# teensy-boom-jr.net
KiCad netlist of a schematic drawn in EAGLE
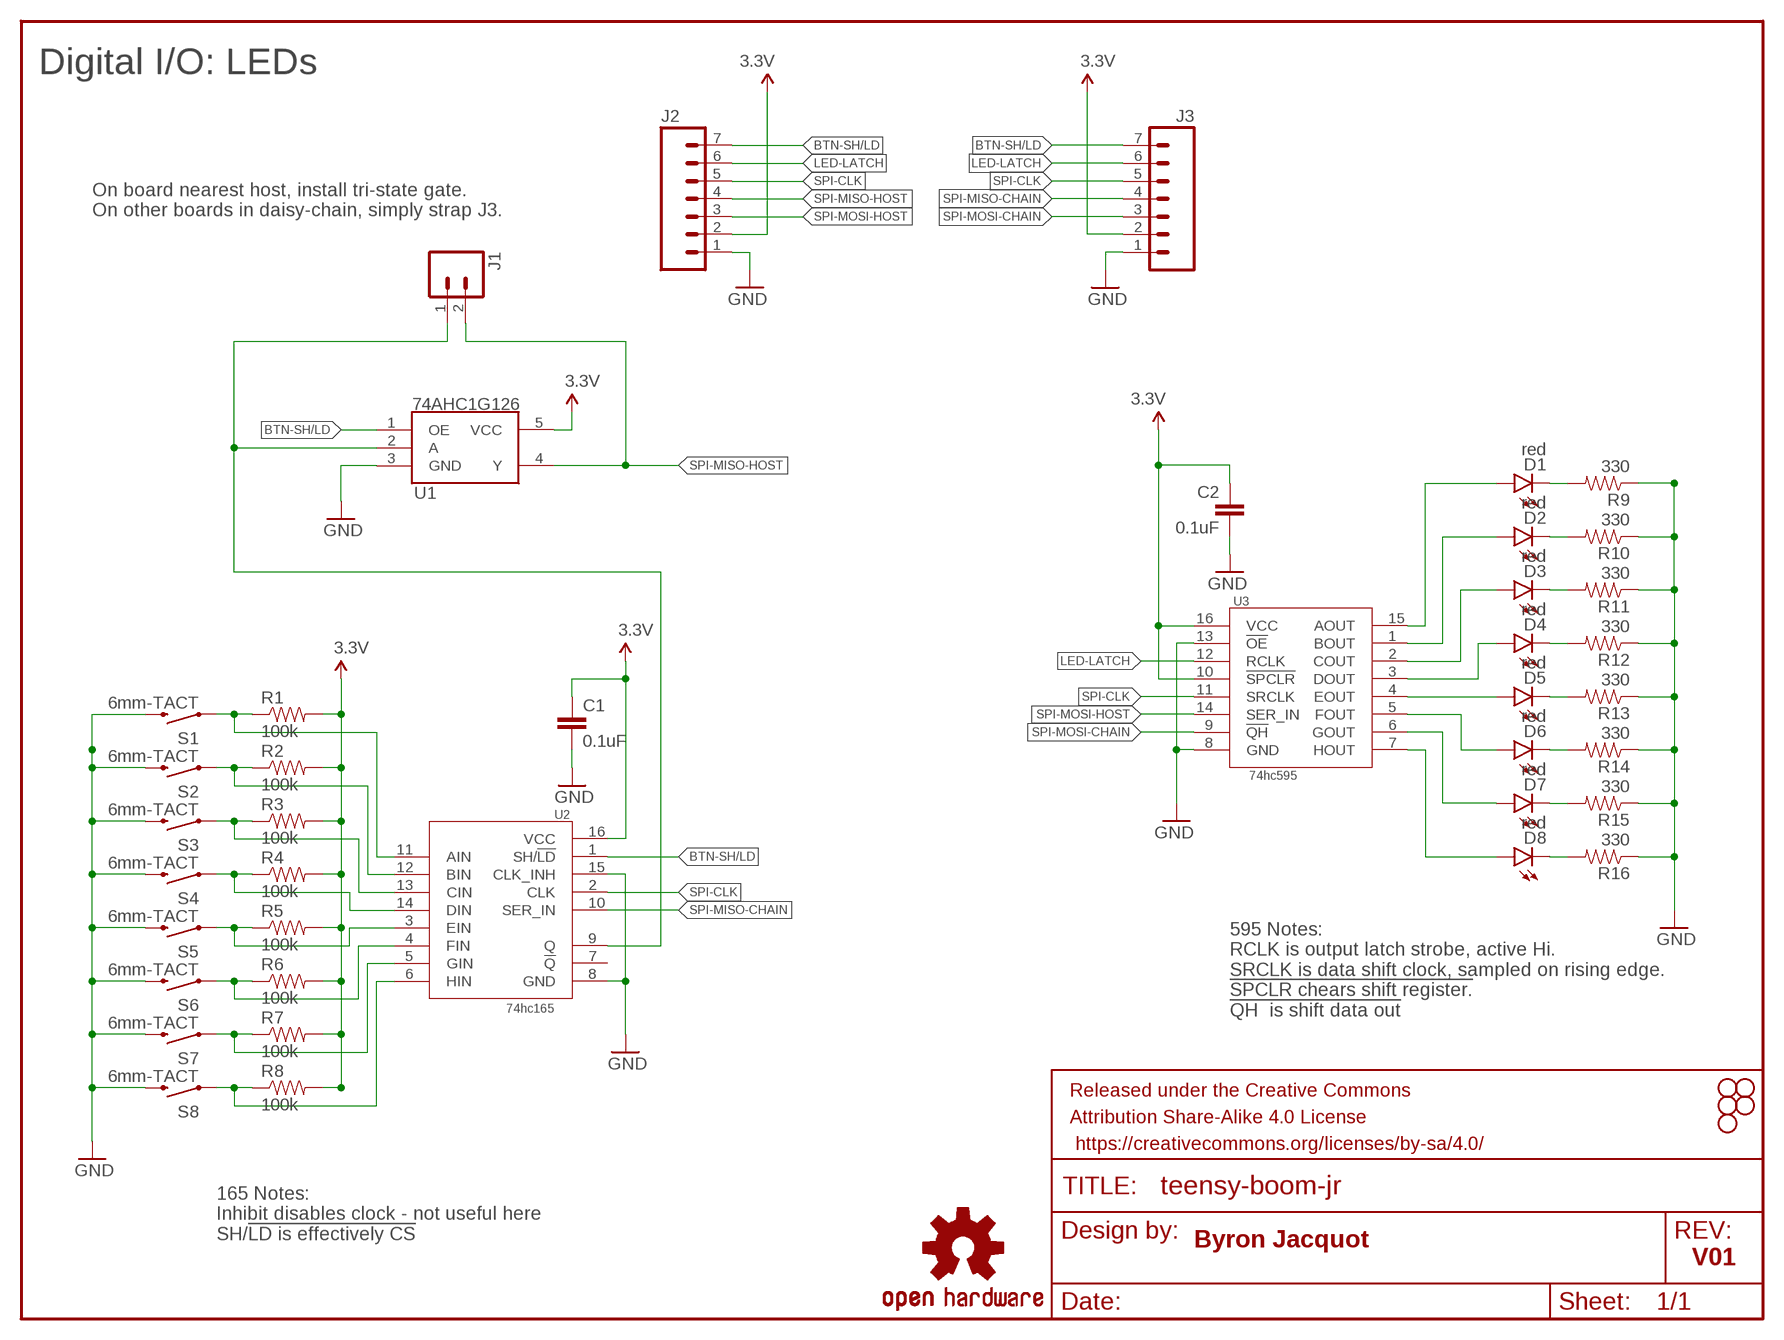
[diagram p0: schematic, sheet 1]

(export (version "E")
  (design (tool "Eeschema 10.0.6"))
  (components
    (comp (ref "C1")
      (value "0.1uF")
      (footprint "eagle-import:0603-CAP")
      (libsource (lib "eagle-import") (part "0.1UF-25V-5%(0603)"))
    )
    (comp (ref "C2")
      (value "0.1uF")
      (footprint "eagle-import:0603-CAP")
      (libsource (lib "eagle-import") (part "0.1UF-25V-5%(0603)"))
    )
    (comp (ref "D1")
      (value "red")
      (footprint "eagle-import:LED3MM-NS")
      (libsource (lib "eagle-import") (part "LED-3MM-NO_SILK"))
    )
    (comp (ref "D2")
      (value "red")
      (footprint "eagle-import:LED3MM-NS")
      (libsource (lib "eagle-import") (part "LED-3MM-NO_SILK"))
    )
    (comp (ref "D3")
      (value "red")
      (footprint "eagle-import:LED3MM-NS")
      (libsource (lib "eagle-import") (part "LED-3MM-NO_SILK"))
    )
    (comp (ref "D4")
      (value "red")
      (footprint "eagle-import:LED3MM-NS")
      (libsource (lib "eagle-import") (part "LED-3MM-NO_SILK"))
    )
    (comp (ref "D5")
      (value "red")
      (footprint "eagle-import:LED3MM-NS")
      (libsource (lib "eagle-import") (part "LED-3MM-NO_SILK"))
    )
    (comp (ref "D6")
      (value "red")
      (footprint "eagle-import:LED3MM-NS")
      (libsource (lib "eagle-import") (part "LED-3MM-NO_SILK"))
    )
    (comp (ref "D7")
      (value "red")
      (footprint "eagle-import:LED3MM-NS")
      (libsource (lib "eagle-import") (part "LED-3MM-NO_SILK"))
    )
    (comp (ref "D8")
      (value "red")
      (footprint "eagle-import:LED3MM-NS")
      (libsource (lib "eagle-import") (part "LED-3MM-NO_SILK"))
    )
    (comp (ref "FRAME1")
      (value "FRAME-LETTERNO_PACKAGE")
      (footprint "eagle-import:DUMMY")
      (fields (field (name "DESIGNER") "Nobody"))
      (libsource (lib "eagle-import") (part "FRAME-LETTERNO_PACKAGE"))
    )
    (comp (ref "H1")
      (value "STAND-OFF")
      (footprint "eagle-import:STAND-OFF")
      (libsource (lib "eagle-import") (part "STAND-OFF"))
    )
    (comp (ref "H2")
      (value "STAND-OFF")
      (footprint "eagle-import:STAND-OFF")
      (libsource (lib "eagle-import") (part "STAND-OFF"))
    )
    (comp (ref "H3")
      (value "STAND-OFF")
      (footprint "eagle-import:STAND-OFF")
      (libsource (lib "eagle-import") (part "STAND-OFF"))
    )
    (comp (ref "H4")
      (value "STAND-OFF")
      (footprint "eagle-import:STAND-OFF")
      (libsource (lib "eagle-import") (part "STAND-OFF"))
    )
    (comp (ref "H5")
      (value "STAND-OFF")
      (footprint "eagle-import:STAND-OFF")
      (libsource (lib "eagle-import") (part "STAND-OFF"))
    )
    (comp (ref "J1")
      (value "M021X02_NO_SILK")
      (footprint "eagle-import:1X02_NO_SILK")
      (libsource (lib "eagle-import") (part "M021X02_NO_SILK"))
    )
    (comp (ref "J2")
      (value "M07NO_SILK")
      (footprint "eagle-import:1X07_NO_SILK")
      (libsource (lib "eagle-import") (part "M07NO_SILK"))
    )
    (comp (ref "J3")
      (value "M07NO_SILK")
      (footprint "eagle-import:1X07_NO_SILK")
      (libsource (lib "eagle-import") (part "M07NO_SILK"))
    )
    (comp (ref "LOGO1")
      (value "OSHW-LOGOS")
      (footprint "eagle-import:OSHW-LOGO-S")
      (libsource (lib "eagle-import") (part "OSHW-LOGOS"))
    )
    (comp (ref "R1")
      (value "100k")
      (footprint "eagle-import:0805")
      (libsource (lib "eagle-import") (part "RESISTOR0805-RES"))
    )
    (comp (ref "R2")
      (value "100k")
      (footprint "eagle-import:0805")
      (libsource (lib "eagle-import") (part "RESISTOR0805-RES"))
    )
    (comp (ref "R3")
      (value "100k")
      (footprint "eagle-import:0805")
      (libsource (lib "eagle-import") (part "RESISTOR0805-RES"))
    )
    (comp (ref "R4")
      (value "100k")
      (footprint "eagle-import:0805")
      (libsource (lib "eagle-import") (part "RESISTOR0805-RES"))
    )
    (comp (ref "R5")
      (value "100k")
      (footprint "eagle-import:0805")
      (libsource (lib "eagle-import") (part "RESISTOR0805-RES"))
    )
    (comp (ref "R6")
      (value "100k")
      (footprint "eagle-import:0805")
      (libsource (lib "eagle-import") (part "RESISTOR0805-RES"))
    )
    (comp (ref "R7")
      (value "100k")
      (footprint "eagle-import:0805")
      (libsource (lib "eagle-import") (part "RESISTOR0805-RES"))
    )
    (comp (ref "R8")
      (value "100k")
      (footprint "eagle-import:0805")
      (libsource (lib "eagle-import") (part "RESISTOR0805-RES"))
    )
    (comp (ref "R9")
      (value "330")
      (footprint "eagle-import:0603-RES")
      (libsource (lib "eagle-import") (part "330OHM1/10W1%(0603)"))
    )
    (comp (ref "R10")
      (value "330")
      (footprint "eagle-import:0603-RES")
      (libsource (lib "eagle-import") (part "330OHM1/10W1%(0603)"))
    )
    (comp (ref "R11")
      (value "330")
      (footprint "eagle-import:0603-RES")
      (libsource (lib "eagle-import") (part "330OHM1/10W1%(0603)"))
    )
    (comp (ref "R12")
      (value "330")
      (footprint "eagle-import:0603-RES")
      (libsource (lib "eagle-import") (part "330OHM1/10W1%(0603)"))
    )
    (comp (ref "R13")
      (value "330")
      (footprint "eagle-import:0603-RES")
      (libsource (lib "eagle-import") (part "330OHM1/10W1%(0603)"))
    )
    (comp (ref "R14")
      (value "330")
      (footprint "eagle-import:0603-RES")
      (libsource (lib "eagle-import") (part "330OHM1/10W1%(0603)"))
    )
    (comp (ref "R15")
      (value "330")
      (footprint "eagle-import:0603-RES")
      (libsource (lib "eagle-import") (part "330OHM1/10W1%(0603)"))
    )
    (comp (ref "R16")
      (value "330")
      (footprint "eagle-import:0603-RES")
      (libsource (lib "eagle-import") (part "330OHM1/10W1%(0603)"))
    )
    (comp (ref "S1")
      (value "6mm-TACT")
      (footprint "eagle-import:TACTILE-PTH-12MM")
      (libsource (lib "eagle-import") (part "SWITCH-MOMENTARY-212MM"))
    )
    (comp (ref "S2")
      (value "6mm-TACT")
      (footprint "eagle-import:TACTILE-PTH-12MM")
      (libsource (lib "eagle-import") (part "SWITCH-MOMENTARY-212MM"))
    )
    (comp (ref "S3")
      (value "6mm-TACT")
      (footprint "eagle-import:TACTILE-PTH-12MM")
      (libsource (lib "eagle-import") (part "SWITCH-MOMENTARY-212MM"))
    )
    (comp (ref "S4")
      (value "6mm-TACT")
      (footprint "eagle-import:TACTILE-PTH-12MM")
      (libsource (lib "eagle-import") (part "SWITCH-MOMENTARY-212MM"))
    )
    (comp (ref "S5")
      (value "6mm-TACT")
      (footprint "eagle-import:TACTILE-PTH-12MM")
      (libsource (lib "eagle-import") (part "SWITCH-MOMENTARY-212MM"))
    )
    (comp (ref "S6")
      (value "6mm-TACT")
      (footprint "eagle-import:TACTILE-PTH-12MM")
      (libsource (lib "eagle-import") (part "SWITCH-MOMENTARY-212MM"))
    )
    (comp (ref "S7")
      (value "6mm-TACT")
      (footprint "eagle-import:TACTILE-PTH-12MM")
      (libsource (lib "eagle-import") (part "SWITCH-MOMENTARY-212MM"))
    )
    (comp (ref "S8")
      (value "6mm-TACT")
      (footprint "eagle-import:TACTILE-PTH-12MM")
      (libsource (lib "eagle-import") (part "SWITCH-MOMENTARY-212MM"))
    )
    (comp (ref "U1")
      (value "74AHC1G126")
      (footprint "eagle-import:SOT23-5")
      (libsource (lib "eagle-import") (part "74AHC1G126"))
    )
    (comp (ref "U2")
      (value "74hc165")
      (footprint "eagle-import:SO16")
      (libsource (lib "eagle-import") (part "74HC165"))
    )
    (comp (ref "U3")
      (value "74hc595")
      (footprint "eagle-import:SO16")
      (libsource (lib "eagle-import") (part "74HC595"))
    )
  )
  (nets
    (net (code "1") (name "3.3V") (class "Default")
      (node (ref "C1") (pin "1") (pinfunction "1_1") (pintype "passive"))
      (node (ref "C2") (pin "1") (pinfunction "1_1") (pintype "passive"))
      (node (ref "J2") (pin "2") (pinfunction "2_2") (pintype "passive"))
      (node (ref "J3") (pin "2") (pinfunction "2_2") (pintype "passive"))
      (node (ref "R1") (pin "2") (pinfunction "2_2") (pintype "passive"))
      (node (ref "R2") (pin "2") (pinfunction "2_2") (pintype "passive"))
      (node (ref "R3") (pin "2") (pinfunction "2_2") (pintype "passive"))
      (node (ref "R4") (pin "2") (pinfunction "2_2") (pintype "passive"))
      (node (ref "R5") (pin "2") (pinfunction "2_2") (pintype "passive"))
      (node (ref "R6") (pin "2") (pinfunction "2_2") (pintype "passive"))
      (node (ref "R7") (pin "2") (pinfunction "2_2") (pintype "passive"))
      (node (ref "R8") (pin "2") (pinfunction "2_2") (pintype "passive"))
      (node (ref "U1") (pin "5") (pinfunction "VCC_5") (pintype "bidirectional"))
      (node (ref "U2") (pin "16") (pinfunction "VCC_16") (pintype "bidirectional"))
      (node (ref "U3") (pin "10") (pinfunction "~{SPCLR}_10") (pintype "bidirectional"))
      (node (ref "U3") (pin "16") (pinfunction "VCC_16") (pintype "bidirectional"))
    )
    (net (code "2") (name "BTN-SH{slash}LD") (class "Default")
      (node (ref "J2") (pin "7") (pinfunction "7_7") (pintype "passive"))
      (node (ref "J3") (pin "7") (pinfunction "7_7") (pintype "passive"))
      (node (ref "U1") (pin "1") (pinfunction "OE_1") (pintype "bidirectional"))
      (node (ref "U2") (pin "1") (pinfunction "SH/~{LD}_1") (pintype "bidirectional"))
    )
    (net (code "3") (name "GND") (class "Default")
      (node (ref "C1") (pin "2") (pinfunction "2_2") (pintype "passive"))
      (node (ref "C2") (pin "2") (pinfunction "2_2") (pintype "passive"))
      (node (ref "J2") (pin "1") (pinfunction "1_1") (pintype "passive"))
      (node (ref "J3") (pin "1") (pinfunction "1_1") (pintype "passive"))
      (node (ref "R10") (pin "1") (pinfunction "1_1") (pintype "passive"))
      (node (ref "R11") (pin "1") (pinfunction "1_1") (pintype "passive"))
      (node (ref "R12") (pin "1") (pinfunction "1_1") (pintype "passive"))
      (node (ref "R13") (pin "1") (pinfunction "1_1") (pintype "passive"))
      (node (ref "R14") (pin "1") (pinfunction "1_1") (pintype "passive"))
      (node (ref "R15") (pin "1") (pinfunction "1_1") (pintype "passive"))
      (node (ref "R16") (pin "1") (pinfunction "1_1") (pintype "passive"))
      (node (ref "R9") (pin "1") (pinfunction "1_1") (pintype "passive"))
      (node (ref "S1") (pin "3") (pinfunction "2_3") (pintype "passive"))
      (node (ref "S2") (pin "3") (pinfunction "2_3") (pintype "passive"))
      (node (ref "S3") (pin "3") (pinfunction "2_3") (pintype "passive"))
      (node (ref "S4") (pin "3") (pinfunction "2_3") (pintype "passive"))
      (node (ref "S5") (pin "3") (pinfunction "2_3") (pintype "passive"))
      (node (ref "S6") (pin "3") (pinfunction "2_3") (pintype "passive"))
      (node (ref "S7") (pin "3") (pinfunction "2_3") (pintype "passive"))
      (node (ref "S8") (pin "3") (pinfunction "2_3") (pintype "passive"))
      (node (ref "U1") (pin "3") (pinfunction "GND_3") (pintype "bidirectional"))
      (node (ref "U2") (pin "15") (pinfunction "CLK_INH_15") (pintype "bidirectional"))
      (node (ref "U2") (pin "8") (pinfunction "GND_8") (pintype "bidirectional"))
      (node (ref "U3") (pin "13") (pinfunction "~{OE}_13") (pintype "bidirectional"))
      (node (ref "U3") (pin "8") (pinfunction "GND_8") (pintype "bidirectional"))
    )
    (net (code "4") (name "LED-LATCH") (class "Default")
      (node (ref "J2") (pin "6") (pinfunction "6_6") (pintype "passive"))
      (node (ref "J3") (pin "6") (pinfunction "6_6") (pintype "passive"))
      (node (ref "U3") (pin "12") (pinfunction "RCLK_12") (pintype "bidirectional"))
    )
    (net (code "5") (name "Net-(D1-C)") (class "Default")
      (node (ref "D1") (pin "K") (pinfunction "C_K") (pintype "passive"))
      (node (ref "R9") (pin "2") (pinfunction "2_2") (pintype "passive"))
    )
    (net (code "6") (name "Net-(D2-C)") (class "Default")
      (node (ref "D2") (pin "K") (pinfunction "C_K") (pintype "passive"))
      (node (ref "R10") (pin "2") (pinfunction "2_2") (pintype "passive"))
    )
    (net (code "7") (name "Net-(D3-C)") (class "Default")
      (node (ref "D3") (pin "K") (pinfunction "C_K") (pintype "passive"))
      (node (ref "R11") (pin "2") (pinfunction "2_2") (pintype "passive"))
    )
    (net (code "8") (name "Net-(D4-C)") (class "Default")
      (node (ref "D4") (pin "K") (pinfunction "C_K") (pintype "passive"))
      (node (ref "R12") (pin "2") (pinfunction "2_2") (pintype "passive"))
    )
    (net (code "9") (name "Net-(D5-C)") (class "Default")
      (node (ref "D5") (pin "K") (pinfunction "C_K") (pintype "passive"))
      (node (ref "R13") (pin "2") (pinfunction "2_2") (pintype "passive"))
    )
    (net (code "10") (name "Net-(D6-C)") (class "Default")
      (node (ref "D6") (pin "K") (pinfunction "C_K") (pintype "passive"))
      (node (ref "R14") (pin "2") (pinfunction "2_2") (pintype "passive"))
    )
    (net (code "11") (name "Net-(D7-C)") (class "Default")
      (node (ref "D7") (pin "K") (pinfunction "C_K") (pintype "passive"))
      (node (ref "R15") (pin "2") (pinfunction "2_2") (pintype "passive"))
    )
    (net (code "12") (name "Net-(D8-C)") (class "Default")
      (node (ref "D8") (pin "K") (pinfunction "C_K") (pintype "passive"))
      (node (ref "R16") (pin "2") (pinfunction "2_2") (pintype "passive"))
    )
    (net (code "13") (name "Net-(U1-A)") (class "Default")
      (node (ref "J1") (pin "1") (pinfunction "1_1") (pintype "passive"))
      (node (ref "U1") (pin "2") (pinfunction "A_2") (pintype "bidirectional"))
      (node (ref "U2") (pin "9") (pinfunction "Q_9") (pintype "bidirectional"))
    )
    (net (code "14") (name "Net-(U2-AIN)") (class "Default")
      (node (ref "R1") (pin "1") (pinfunction "1_1") (pintype "passive"))
      (node (ref "S1") (pin "1") (pinfunction "1_1") (pintype "passive"))
      (node (ref "U2") (pin "11") (pinfunction "AIN_11") (pintype "bidirectional"))
    )
    (net (code "15") (name "Net-(U2-BIN)") (class "Default")
      (node (ref "R2") (pin "1") (pinfunction "1_1") (pintype "passive"))
      (node (ref "S2") (pin "1") (pinfunction "1_1") (pintype "passive"))
      (node (ref "U2") (pin "12") (pinfunction "BIN_12") (pintype "bidirectional"))
    )
    (net (code "16") (name "Net-(U2-CIN)") (class "Default")
      (node (ref "R3") (pin "1") (pinfunction "1_1") (pintype "passive"))
      (node (ref "S3") (pin "1") (pinfunction "1_1") (pintype "passive"))
      (node (ref "U2") (pin "13") (pinfunction "CIN_13") (pintype "bidirectional"))
    )
    (net (code "17") (name "Net-(U2-DIN)") (class "Default")
      (node (ref "R4") (pin "1") (pinfunction "1_1") (pintype "passive"))
      (node (ref "S4") (pin "1") (pinfunction "1_1") (pintype "passive"))
      (node (ref "U2") (pin "14") (pinfunction "DIN_14") (pintype "bidirectional"))
    )
    (net (code "18") (name "Net-(U2-EIN)") (class "Default")
      (node (ref "R5") (pin "1") (pinfunction "1_1") (pintype "passive"))
      (node (ref "S5") (pin "1") (pinfunction "1_1") (pintype "passive"))
      (node (ref "U2") (pin "3") (pinfunction "EIN_3") (pintype "bidirectional"))
    )
    (net (code "19") (name "Net-(U2-FIN)") (class "Default")
      (node (ref "R6") (pin "1") (pinfunction "1_1") (pintype "passive"))
      (node (ref "S6") (pin "1") (pinfunction "1_1") (pintype "passive"))
      (node (ref "U2") (pin "4") (pinfunction "FIN_4") (pintype "bidirectional"))
    )
    (net (code "20") (name "Net-(U2-GIN)") (class "Default")
      (node (ref "R7") (pin "1") (pinfunction "1_1") (pintype "passive"))
      (node (ref "S7") (pin "1") (pinfunction "1_1") (pintype "passive"))
      (node (ref "U2") (pin "5") (pinfunction "GIN_5") (pintype "bidirectional"))
    )
    (net (code "21") (name "Net-(U2-HIN)") (class "Default")
      (node (ref "R8") (pin "1") (pinfunction "1_1") (pintype "passive"))
      (node (ref "S8") (pin "1") (pinfunction "1_1") (pintype "passive"))
      (node (ref "U2") (pin "6") (pinfunction "HIN_6") (pintype "bidirectional"))
    )
    (net (code "22") (name "Net-(U3-AOUT)") (class "Default")
      (node (ref "D1") (pin "A") (pinfunction "A_A") (pintype "passive"))
      (node (ref "U3") (pin "15") (pinfunction "AOUT_15") (pintype "bidirectional"))
    )
    (net (code "23") (name "Net-(U3-BOUT)") (class "Default")
      (node (ref "D2") (pin "A") (pinfunction "A_A") (pintype "passive"))
      (node (ref "U3") (pin "1") (pinfunction "BOUT_1") (pintype "bidirectional"))
    )
    (net (code "24") (name "Net-(U3-COUT)") (class "Default")
      (node (ref "D3") (pin "A") (pinfunction "A_A") (pintype "passive"))
      (node (ref "U3") (pin "2") (pinfunction "COUT_2") (pintype "bidirectional"))
    )
    (net (code "25") (name "Net-(U3-DOUT)") (class "Default")
      (node (ref "D4") (pin "A") (pinfunction "A_A") (pintype "passive"))
      (node (ref "U3") (pin "3") (pinfunction "DOUT_3") (pintype "bidirectional"))
    )
    (net (code "26") (name "Net-(U3-EOUT)") (class "Default")
      (node (ref "D5") (pin "A") (pinfunction "A_A") (pintype "passive"))
      (node (ref "U3") (pin "4") (pinfunction "EOUT_4") (pintype "bidirectional"))
    )
    (net (code "27") (name "Net-(U3-FOUT)") (class "Default")
      (node (ref "D6") (pin "A") (pinfunction "A_A") (pintype "passive"))
      (node (ref "U3") (pin "5") (pinfunction "FOUT_5") (pintype "bidirectional"))
    )
    (net (code "28") (name "Net-(U3-GOUT)") (class "Default")
      (node (ref "D7") (pin "A") (pinfunction "A_A") (pintype "passive"))
      (node (ref "U3") (pin "6") (pinfunction "GOUT_6") (pintype "bidirectional"))
    )
    (net (code "29") (name "Net-(U3-HOUT)") (class "Default")
      (node (ref "D8") (pin "A") (pinfunction "A_A") (pintype "passive"))
      (node (ref "U3") (pin "7") (pinfunction "HOUT_7") (pintype "bidirectional"))
    )
    (net (code "30") (name "SPI-CLK") (class "Default")
      (node (ref "J2") (pin "5") (pinfunction "5_5") (pintype "passive"))
      (node (ref "J3") (pin "5") (pinfunction "5_5") (pintype "passive"))
      (node (ref "U2") (pin "2") (pinfunction "CLK_2") (pintype "bidirectional"))
      (node (ref "U3") (pin "11") (pinfunction "SRCLK_11") (pintype "bidirectional"))
    )
    (net (code "31") (name "SPI-MISO-CHAIN") (class "Default")
      (node (ref "J3") (pin "4") (pinfunction "4_4") (pintype "passive"))
      (node (ref "U2") (pin "10") (pinfunction "SER_IN_10") (pintype "bidirectional"))
    )
    (net (code "32") (name "SPI-MISO-HOST") (class "Default")
      (node (ref "J1") (pin "2") (pinfunction "2_2") (pintype "passive"))
      (node (ref "J2") (pin "4") (pinfunction "4_4") (pintype "passive"))
      (node (ref "U1") (pin "4") (pinfunction "Y_4") (pintype "bidirectional"))
    )
    (net (code "33") (name "SPI-MOSI-CHAIN") (class "Default")
      (node (ref "J3") (pin "3") (pinfunction "3_3") (pintype "passive"))
      (node (ref "U3") (pin "9") (pinfunction "~{QH}_9") (pintype "bidirectional"))
    )
    (net (code "34") (name "SPI-MOSI-HOST") (class "Default")
      (node (ref "J2") (pin "3") (pinfunction "3_3") (pintype "passive"))
      (node (ref "U3") (pin "14") (pinfunction "SER_IN_14") (pintype "bidirectional"))
    )
    (net (code "35") (name "unconnected-(U2-~{Q}-Pad7)") (class "Default")
      (node (ref "U2") (pin "7") (pinfunction "~{Q}_7") (pintype "bidirectional"))
    )
  )
)
